# Breadboard.net
KiCad netlist of a schematic drawn in EAGLE
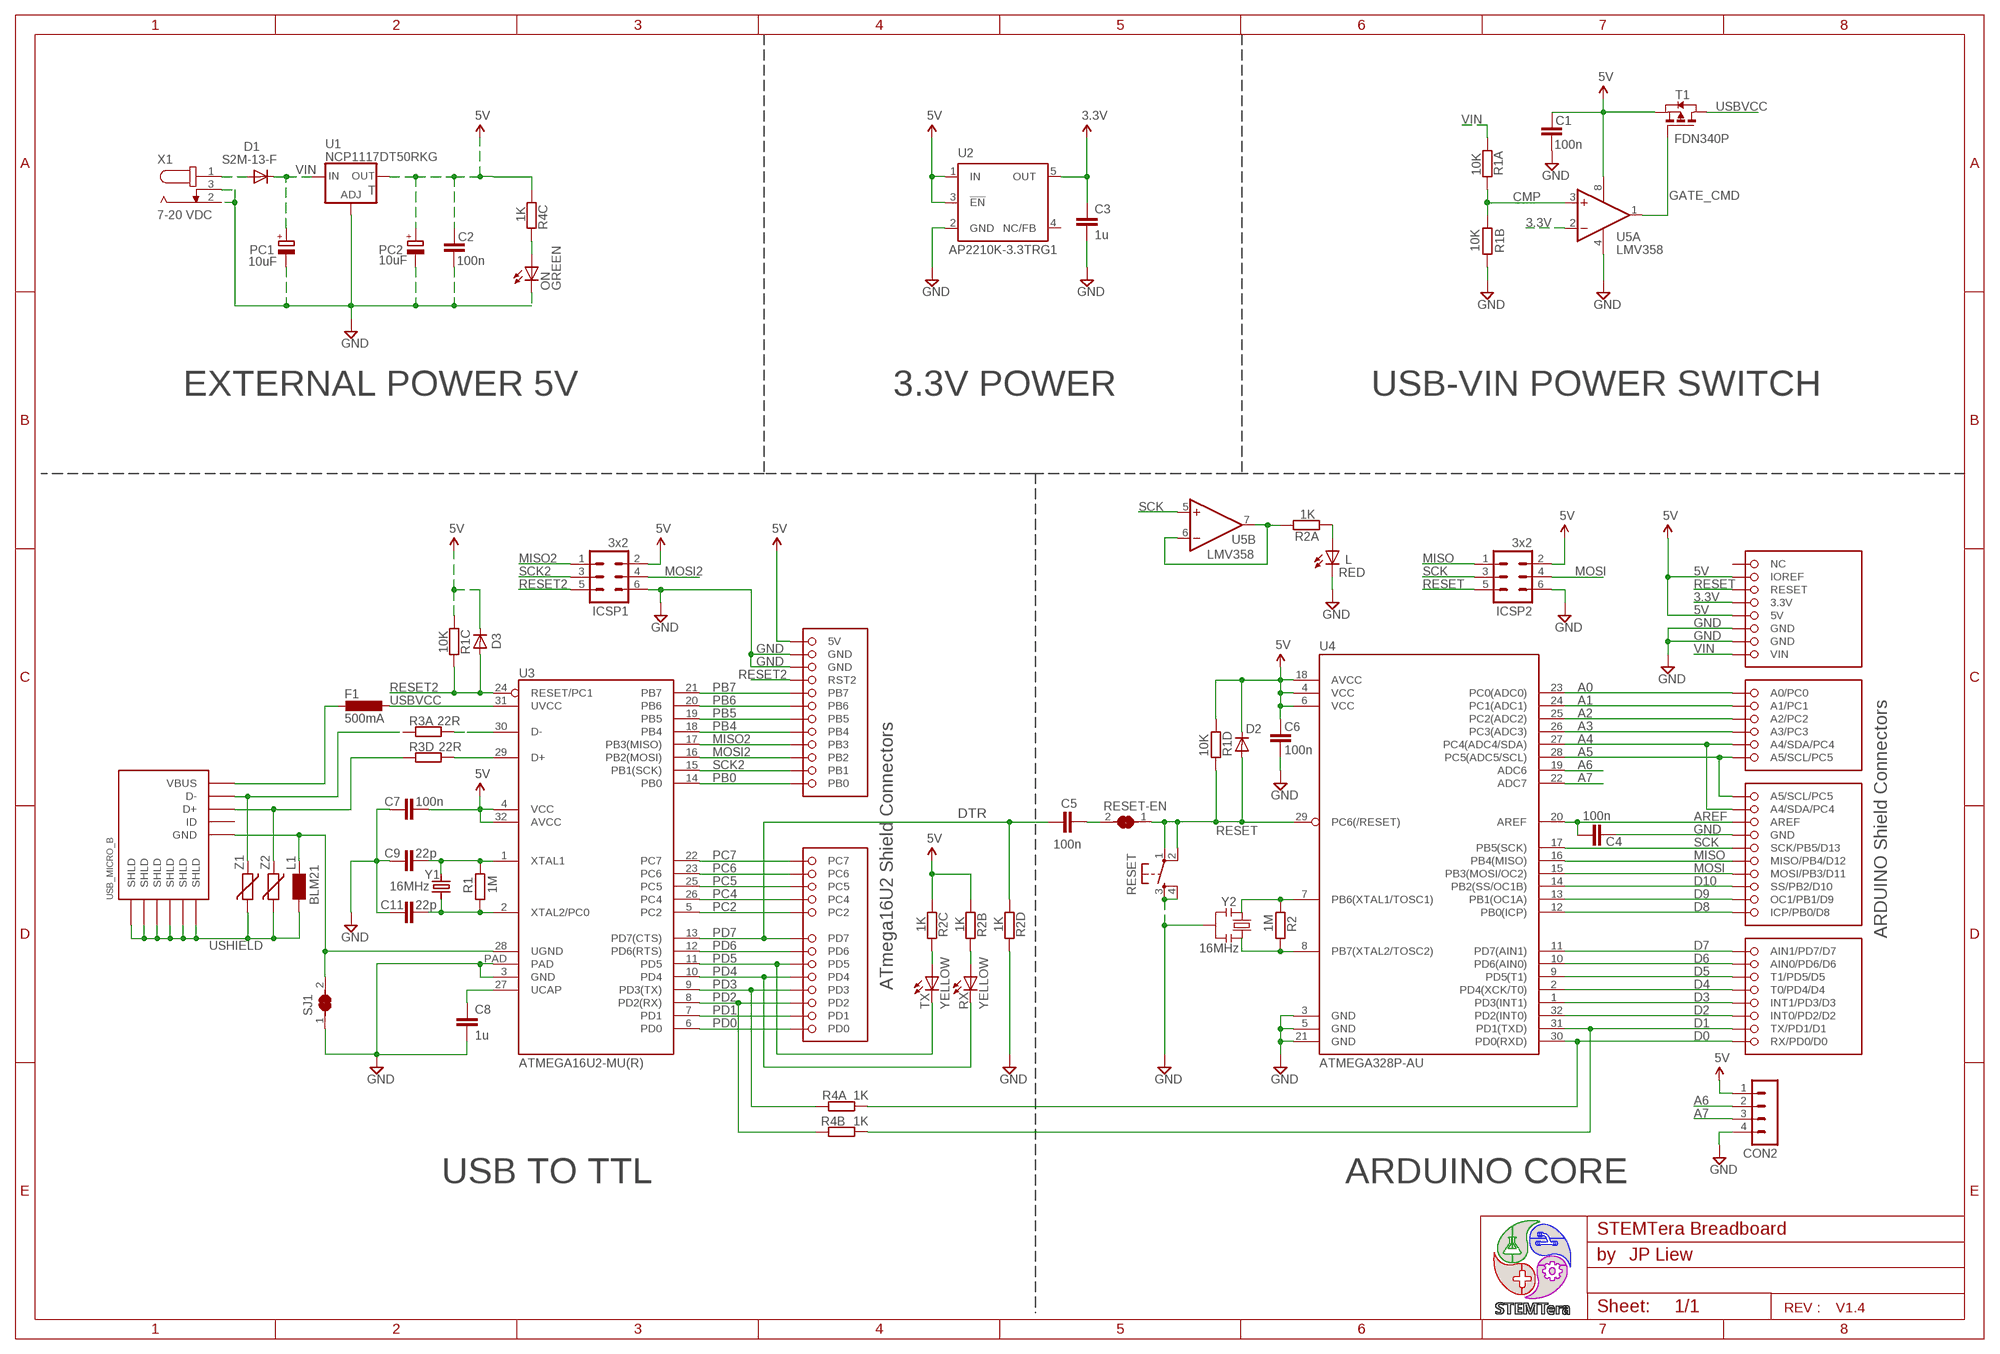
[diagram p0: schematic, sheet 1]

(export (version "E")
  (design (tool "Eeschema 10.0.6"))
  (components
    (comp (ref "C1")
      (value "100n")
      (footprint "eagle-import:C0603")
      (description "CAP CER 0.1UF 50V X7R 0603")
      (fields (field (name "MF") "Yageo") (field (name "MPN") "CC0603KRX7R9BB104"))
      (libsource (lib "eagle-import") (part "C-EUC0603"))
    )
    (comp (ref "C2")
      (value "100n")
      (footprint "eagle-import:C0603")
      (description "CAP CER 0.1UF 50V X7R 0603")
      (fields (field (name "MF") "Yageo") (field (name "MPN") "CC0603KRX7R9BB104"))
      (libsource (lib "eagle-import") (part "C-EUC0603"))
    )
    (comp (ref "C3")
      (value "1u")
      (footprint "eagle-import:C0603")
      (description "CAP CER 1UF 10V X5R 0603")
      (fields (field (name "MF") "Yageo") (field (name "MPN") "CC0603KRX5R6BB105"))
      (libsource (lib "eagle-import") (part "C-EUC0603"))
    )
    (comp (ref "C4")
      (value "100n")
      (footprint "eagle-import:C0603")
      (description "CAP CER 0.1UF 50V X7R 0603")
      (fields (field (name "MF") "Yageo") (field (name "MPN") "CC0603KRX7R9BB104"))
      (libsource (lib "eagle-import") (part "C-EUC0603"))
    )
    (comp (ref "C5")
      (value "100n")
      (footprint "eagle-import:C0603")
      (description "CAP CER 0.1UF 50V X7R 0603")
      (fields (field (name "MF") "Yageo") (field (name "MPN") "CC0603KRX7R9BB104"))
      (libsource (lib "eagle-import") (part "C-EUC0603"))
    )
    (comp (ref "C6")
      (value "100n")
      (footprint "eagle-import:C0603")
      (description "CAP CER 0.1UF 50V X7R 0603")
      (fields (field (name "MF") "Yageo") (field (name "MPN") "CC0603KRX7R9BB104"))
      (libsource (lib "eagle-import") (part "C-EUC0603"))
    )
    (comp (ref "C7")
      (value "100n")
      (footprint "eagle-import:C0603")
      (description "CAP CER 0.1UF 50V X7R 0603")
      (fields (field (name "MF") "Yageo") (field (name "MPN") "CC0603KRX7R9BB104"))
      (libsource (lib "eagle-import") (part "C-EUC0603"))
    )
    (comp (ref "C8")
      (value "1u")
      (footprint "eagle-import:C0603")
      (description "CAP CER 1UF 10V X5R 0603")
      (fields (field (name "MF") "Yageo") (field (name "MPN") "CC0603KRX5R6BB105"))
      (libsource (lib "eagle-import") (part "C-EUC0603"))
    )
    (comp (ref "C9")
      (value "22p")
      (footprint "eagle-import:C0603")
      (description "CAP CER 22PF 50V NP0 0603")
      (fields (field (name "MF") "AVX") (field (name "MPN") "06035A220JAT2A"))
      (libsource (lib "eagle-import") (part "C-EUC0603"))
    )
    (comp (ref "C11")
      (value "22p")
      (footprint "eagle-import:C0603")
      (description "CAP CER 22PF 50V NP0 0603")
      (fields (field (name "MF") "AVX") (field (name "MPN") "06035A220JAT2A"))
      (libsource (lib "eagle-import") (part "C-EUC0603"))
    )
    (comp (ref "CON1")
      (value "STEMTERA")
      (footprint "eagle-import:STEMTERA")
      (fields (field (name "MF") "NOT INSTALLED") (field (name "MPN") "NOT INSTALLED"))
      (libsource (lib "eagle-import") (part "STEMTERA"))
    )
    (comp (ref "CON2")
      (value "MA04-1")
      (footprint "eagle-import:MA04-1-SMD")
      (libsource (lib "eagle-import") (part "MA04-1"))
    )
    (comp (ref "D1")
      (value "S2M-13-F")
      (footprint "eagle-import:SMB")
      (description "DIODE GEN PURP 1KV 1.5A SMB")
      (fields (field (name "MF") "Diodes Inc"))
      (libsource (lib "eagle-import") (part "DIODE-SMB"))
    )
    (comp (ref "D2")
      (value "CD1206-S01575")
      (footprint "eagle-import:MINIMELF")
      (description "DIODE GEN PURP 100V 150MA 1206")
      (fields (field (name "MF") "Bourns Inc"))
      (libsource (lib "eagle-import") (part "DIODE-MINIMELF"))
    )
    (comp (ref "D3")
      (value "CD1206-S01575")
      (footprint "eagle-import:MINIMELF")
      (description "DIODE GEN PURP 100V 150MA 1206")
      (fields (field (name "MF") "Bourns Inc"))
      (libsource (lib "eagle-import") (part "DIODE-MINIMELF"))
    )
    (comp (ref "F1")
      (value "500mA")
      (footprint "eagle-import:L1812")
      (description "PTC RESETTABLE .50A 15V 1812")
      (fields (field (name "MF") "Bourns Inc") (field (name "MPN") "MF-MSMF050-2"))
      (libsource (lib "eagle-import") (part "L-EUL1812"))
    )
    (comp (ref "ICSP1")
      (value "3x2")
      (footprint "eagle-import:MA03-2")
      (description "ATmega16U2 ISP Conn")
      (fields (field (name "MF") "NOT INSTALLED") (field (name "MPN") "NOT INSTALLED"))
      (libsource (lib "eagle-import") (part "MA03-2"))
    )
    (comp (ref "ICSP2")
      (value "3x2")
      (footprint "eagle-import:MA03-2")
      (description "ATmega328 ISP Conn")
      (fields (field (name "MF") "NOT INSTALLED") (field (name "MPN") "NOT INSTALLED"))
      (libsource (lib "eagle-import") (part "MA03-2"))
    )
    (comp (ref "L")
      (value "RED")
      (footprint "eagle-import:LED3MM")
      (description "LED, 2MM, RED, 8MCD, 617NM")
      (fields (field (name "MF") "Kingbright") (field (name "MPN") "L-13ID"))
      (libsource (lib "eagle-import") (part "LED3MM"))
    )
    (comp (ref "L1")
      (value "BLM21")
      (footprint "eagle-import:0805")
      (description "FERRITE CHIP 220 OHM 0805")
      (fields (field (name "MF") "Murata") (field (name "MPN") "BLM21PG221SN1D"))
      (libsource (lib "eagle-import") (part "WE-CBF-0805"))
    )
    (comp (ref "ON")
      (value "GREEN")
      (footprint "eagle-import:LED3MM")
      (description "LED, GREEN, 2MM, 12MCD, 568NM")
      (fields (field (name "MF") "Kingbright") (field (name "MPN") "L-13GD"))
      (libsource (lib "eagle-import") (part "LED3MM"))
    )
    (comp (ref "PC1")
      (value "10uF")
      (footprint "eagle-import:CT6032")
      (description "CAP TANT 10UF 25V 20%")
      (fields (field (name "MF") "Kemet") (field (name "MPN") "T491C106M025AT7280"))
      (libsource (lib "eagle-import") (part "CAP_POL-CT6032"))
    )
    (comp (ref "PC2")
      (value "10uF")
      (footprint "eagle-import:CT6032")
      (description "CAP TANT 10UF 25V 20%")
      (fields (field (name "MF") "Kemet") (field (name "MPN") "T491C106M025AT7280"))
      (libsource (lib "eagle-import") (part "CAP_POL-CT6032"))
    )
    (comp (ref "R1")
      (value "1M")
      (footprint "eagle-import:R0603")
      (description "RES SMD 1M OHM 1% 1/10W 0603")
      (fields (field (name "MF") "Yageo") (field (name "MPN") "RC0603FR-071ML"))
      (libsource (lib "eagle-import") (part "R-EU_R0603"))
    )
    (comp (ref "R1A")
      (value "10K")
      (footprint "eagle-import:R0603")
      (description "RES SMD 10K OHM 1% 1/10W 0603")
      (fields (field (name "MF") "Yageo") (field (name "MPN") "RC0603FR-0710KL"))
      (libsource (lib "eagle-import") (part "R-EU_R0603"))
    )
    (comp (ref "R1B")
      (value "10K")
      (footprint "eagle-import:R0603")
      (description "RES SMD 10K OHM 1% 1/10W 0603")
      (fields (field (name "MF") "Yageo") (field (name "MPN") "RC0603FR-0710KL"))
      (libsource (lib "eagle-import") (part "R-EU_R0603"))
    )
    (comp (ref "R1C")
      (value "10K")
      (footprint "eagle-import:R0603")
      (description "RES SMD 10K OHM 1% 1/10W 0603")
      (fields (field (name "MF") "Yageo") (field (name "MPN") "RC0603FR-0710KL"))
      (libsource (lib "eagle-import") (part "R-EU_R0603"))
    )
    (comp (ref "R1D")
      (value "10K")
      (footprint "eagle-import:R0603")
      (description "RES SMD 10K OHM 1% 1/10W 0603")
      (fields (field (name "MF") "Yageo") (field (name "MPN") "RC0603FR-0710KL"))
      (libsource (lib "eagle-import") (part "R-EU_R0603"))
    )
    (comp (ref "R2")
      (value "1M")
      (footprint "eagle-import:R0603")
      (description "RES SMD 1M OHM 1% 1/10W 0603")
      (fields (field (name "MF") "Yageo") (field (name "MPN") "RC0603FR-071ML"))
      (libsource (lib "eagle-import") (part "R-EU_R0603"))
    )
    (comp (ref "R2A")
      (value "1K")
      (footprint "eagle-import:R0603")
      (description "RES SMD 1K OHM 1% 1/10W 0603")
      (fields (field (name "MF") "Yageo") (field (name "MPN") "RC0603FR-071KL"))
      (libsource (lib "eagle-import") (part "R-EU_R0603"))
    )
    (comp (ref "R2B")
      (value "1K")
      (footprint "eagle-import:R0603")
      (description "RES SMD 1K OHM 1% 1/10W 0603")
      (fields (field (name "MF") "Yageo") (field (name "MPN") "RC0603FR-071KL"))
      (libsource (lib "eagle-import") (part "R-EU_R0603"))
    )
    (comp (ref "R2C")
      (value "1K")
      (footprint "eagle-import:R0603")
      (description "RES SMD 1K OHM 1% 1/10W 0603")
      (fields (field (name "MF") "Yageo") (field (name "MPN") "RC0603FR-071KL"))
      (libsource (lib "eagle-import") (part "R-EU_R0603"))
    )
    (comp (ref "R2D")
      (value "1K")
      (footprint "eagle-import:R0603")
      (description "RES SMD 1K OHM 1% 1/10W 0603")
      (fields (field (name "MF") "Yageo") (field (name "MPN") "RC0603FR-071KL"))
      (libsource (lib "eagle-import") (part "R-EU_R0603"))
    )
    (comp (ref "R3A")
      (value "22R")
      (footprint "eagle-import:R0603")
      (description "RES SMD 22 OHM 1% 1/10W 0603")
      (fields (field (name "MF") "Yageo") (field (name "MPN") "RC0603FR-0722RL"))
      (libsource (lib "eagle-import") (part "R-EU_R0603"))
    )
    (comp (ref "R3D")
      (value "22R")
      (footprint "eagle-import:R0603")
      (description "RES SMD 22 OHM 1% 1/10W 0603")
      (fields (field (name "MF") "Yageo") (field (name "MPN") "RC0603FR-0722RL"))
      (libsource (lib "eagle-import") (part "R-EU_R0603"))
    )
    (comp (ref "R4A")
      (value "1K")
      (footprint "eagle-import:R0603")
      (description "RES SMD 1K OHM 1% 1/10W 0603")
      (fields (field (name "MF") "Yageo") (field (name "MPN") "RC0603FR-071KL"))
      (libsource (lib "eagle-import") (part "R-EU_R0603"))
    )
    (comp (ref "R4B")
      (value "1K")
      (footprint "eagle-import:R0603")
      (description "RES SMD 1K OHM 1% 1/10W 0603")
      (fields (field (name "MF") "Yageo") (field (name "MPN") "RC0603FR-071KL"))
      (libsource (lib "eagle-import") (part "R-EU_R0603"))
    )
    (comp (ref "R4C")
      (value "1K")
      (footprint "eagle-import:R0603")
      (description "RES SMD 1K OHM 1% 1/10W 0603")
      (fields (field (name "MF") "Yageo") (field (name "MPN") "RC0603FR-071KL"))
      (libsource (lib "eagle-import") (part "R-EU_R0603"))
    )
    (comp (ref "RESET")
      (value "PUSH_BUTTON-ESWITCH_TL6120DF300QG")
      (footprint "eagle-import:PUSH_BUTTON-ESWITCH_TL6120DF300QG")
      (fields (field (name "MF") "E-Switch") (field (name "MPN") "TL6120DF300QG"))
      (libsource (lib "eagle-import") (part "PUSH_BUTTON-ESWITCH_TL6120DF300QG"))
    )
    (comp (ref "RESET-EN")
      (value "Jumper")
      (footprint "eagle-import:SOLDER_JUMPER_NC")
      (description "RESET ENABLE PCB JUMPER")
      (fields (field (name "MF") "NOT INSTALLED"))
      (libsource (lib "eagle-import") (part "SOLDER_JUMPER_NC"))
    )
    (comp (ref "RX")
      (value "YELLOW")
      (footprint "eagle-import:LED3MM")
      (description "LED, 2MM, YELLOW, 8MCD, 588NM")
      (fields (field (name "MF") "Kingbright") (field (name "MPN") "L-13YD"))
      (libsource (lib "eagle-import") (part "LED3MM"))
    )
    (comp (ref "SJ1")
      (value "Jumper")
      (footprint "eagle-import:SOLDER_JUMPER_NC")
      (description "USB SHIELD GROUND PCB JUMPER")
      (fields (field (name "MF") "NOT INSTALLED"))
      (libsource (lib "eagle-import") (part "SOLDER_JUMPER_NC"))
    )
    (comp (ref "T1")
      (value "FDN340P")
      (footprint "eagle-import:SOT-23")
      (description "MOSFET P-CH 20V 2A SSOT3")
      (fields (field (name "MF") "Fairchild") (field (name "MPN") "FDN340P"))
      (libsource (lib "eagle-import") (part "PMOSSOT23"))
    )
    (comp (ref "TX")
      (value "YELLOW")
      (footprint "eagle-import:LED3MM")
      (description "LED, YELLOW, 2MM, 8MCD, 590NM")
      (fields (field (name "MF") "Kingbright") (field (name "MPN") "L-13YD"))
      (libsource (lib "eagle-import") (part "LED3MM"))
    )
    (comp (ref "U1")
      (value "NCP1117DT50RKG")
      (footprint "eagle-import:DPACK")
      (description "IC REG LDO 5V 1A DPAK")
      (fields (field (name "MF") "ON Semiconductor"))
      (libsource (lib "eagle-import") (part "LD117A?DT-TR"))
    )
    (comp (ref "U2")
      (value "AP2210K-3.3TRG1")
      (footprint "eagle-import:SOT23-DBV")
      (description "IC REG LDO 3.3V 0.3A SOT25")
      (fields
        (field (name "MF") "TEXAS INSTRUMENTS")
        (field (name "MPN") "TPS77001DBVT")
        (field (name "MF_1") "Diodes Inc")
        (field (name "MPN_1") "AP2210K-3.3TRG1")
      )
      (libsource (lib "eagle-import") (part "TPS77001"))
    )
    (comp (ref "U3")
      (value "ATMEGA16U2-MU(R)")
      (footprint "eagle-import:QFN32")
      (description "IC MCU 8BIT 16KB FLASH 32QFN")
      (fields (field (name "MF") "Atmel") (field (name "MPN") "ATMEGA16U2-MU"))
      (libsource (lib "eagle-import") (part "ATMEGAXXU2-MU"))
    )
    (comp (ref "U4")
      (value "ATMEGA328P-AU")
      (footprint "eagle-import:TQFP32-7MM_0.8MM")
      (description "IC MCU 8BIT 32KB FLASH 32TQFP")
      (fields (field (name "MF") "Atmel") (field (name "MPN") "ATmega328P-AUR"))
      (libsource (lib "eagle-import") (part "ATMEGAXX8-32PIN"))
    )
    (comp (ref "U5")
      (value "LMV358")
      (footprint "eagle-import:SOIC08_3.8MM")
      (description "IC OPAMP GP 1MHZ RRO 8SOP")
      (fields
        (field (name "MF") "Diodes Incorporated")
        (field (name "MPN") "LMV358SG-13")
        (field (name "OC_DIGIKEY") "LMV358SG-13DITR-ND")
        (field (name "URL") "http://www.digikey.com/product-detail/en/LMV358SG-13/LMV358SG-13DITR-ND/2182560")
      )
      (libsource (lib "eagle-import") (part "LM358-SO8"))
    )
    (comp (ref "USB_MICRO_B")
      (value "CONN_USB-FCI_10118193-0001LF")
      (footprint "eagle-import:CONN_USB_MICRO_B_10118193-0001LF")
      (fields
        (field (name "MF") "FCI")
        (field (name "MPN") "10118193-0001LF")
        (field (name "MPN_1") "10118193-0001LF")
      )
      (libsource (lib "eagle-import") (part "CONN_USB-FCI_10118193-0001LF"))
    )
    (comp (ref "X1")
      (value "CONN_JACK-SINGLE_SIDED")
      (footprint "eagle-import:CONN_JACK_PJ-051A-SINGLE_SIDED")
      (fields (field (name "MF") "CUI Inc") (field (name "MPN") "PJ-051A"))
      (libsource (lib "eagle-import") (part "CONN_JACK-SINGLE_SIDED"))
    )
    (comp (ref "Y1")
      (value "16MHz")
      (footprint "eagle-import:HC49US-SMD-2.5MM")
      (description "Crystal 16.0000MHz 20ppm 18pF")
      (fields (field (name "MF") "Abracon") (field (name "MPN") "ABLS3-16.000MHZ-D4Y-T"))
      (libsource (lib "eagle-import") (part "CRYSTAL-HC49US_2.5MM"))
    )
    (comp (ref "Y2")
      (value "16MHz")
      (footprint "eagle-import:CSTCE_V")
      (description "CER RESONATOR 16.0MHZ SMD")
      (fields (field (name "MF") "Murata") (field (name "MPN") "CSTCE16M0V53-R0"))
      (libsource (lib "eagle-import") (part "RESONATORS-CSCTE_V"))
    )
    (comp (ref "Z1")
      (value "VARISTORCN0603")
      (footprint "eagle-import:CT_CN0603")
      (description "VARISTOR 0603")
      (fields (field (name "MF") "Bourns Inc") (field (name "MPN") "CG0603MLC-05E"))
      (libsource (lib "eagle-import") (part "VARISTORCN0603"))
    )
    (comp (ref "Z2")
      (value "VARISTORCN0603")
      (footprint "eagle-import:CT_CN0603")
      (description "VARISTOR 0603")
      (fields (field (name "MF") "Bourns Inc") (field (name "MPN") "CG0603MLC-05E"))
      (libsource (lib "eagle-import") (part "VARISTORCN0603"))
    )
  )
  (nets
    (net (code "1") (name "/A0") (class "Default")
      (node (ref "CON1") (pin "A0") (pinfunction "A0/PC0_A0") (pintype "bidirectional"))
      (node (ref "U4") (pin "23") (pinfunction "PC0(ADC0)_23") (pintype "bidirectional"))
    )
    (net (code "2") (name "/A1") (class "Default")
      (node (ref "CON1") (pin "A1") (pinfunction "A1/PC1_A1") (pintype "bidirectional"))
      (node (ref "U4") (pin "24") (pinfunction "PC1(ADC1)_24") (pintype "bidirectional"))
    )
    (net (code "3") (name "/A2") (class "Default")
      (node (ref "CON1") (pin "A2") (pinfunction "A2/PC2_A2") (pintype "bidirectional"))
      (node (ref "U4") (pin "25") (pinfunction "PC2(ADC2)_25") (pintype "bidirectional"))
    )
    (net (code "4") (name "/A3") (class "Default")
      (node (ref "CON1") (pin "A3") (pinfunction "A3/PC3_A3") (pintype "bidirectional"))
      (node (ref "U4") (pin "26") (pinfunction "PC3(ADC3)_26") (pintype "bidirectional"))
    )
    (net (code "5") (name "/A4") (class "Default")
      (node (ref "CON1") (pin "A4@1") (pinfunction "A4/SDA/PC4_A4@1") (pintype "bidirectional"))
      (node (ref "CON1") (pin "A4@2") (pinfunction "A4/SDA/PC4_A4@2") (pintype "bidirectional"))
      (node (ref "U4") (pin "27") (pinfunction "PC4(ADC4/SDA)_27") (pintype "bidirectional"))
    )
    (net (code "6") (name "/A5") (class "Default")
      (node (ref "CON1") (pin "A5@1") (pinfunction "A5/SCL/PC5_A5@1") (pintype "bidirectional"))
      (node (ref "CON1") (pin "A5@2") (pinfunction "A5/SCL/PC5_A5@2") (pintype "bidirectional"))
      (node (ref "U4") (pin "28") (pinfunction "PC5(ADC5/SCL)_28") (pintype "bidirectional"))
    )
    (net (code "7") (name "/A6") (class "Default")
      (node (ref "CON2") (pin "2") (pinfunction "2_2") (pintype "passive"))
      (node (ref "U4") (pin "19") (pinfunction "ADC6_19") (pintype "bidirectional"))
    )
    (net (code "8") (name "/A7") (class "Default")
      (node (ref "CON2") (pin "3") (pinfunction "3_3") (pintype "passive"))
      (node (ref "U4") (pin "22") (pinfunction "ADC7_22") (pintype "bidirectional"))
    )
    (net (code "9") (name "/AREF") (class "Default")
      (node (ref "C4") (pin "2") (pinfunction "2_2") (pintype "passive"))
      (node (ref "CON1") (pin "AREF") (pinfunction "AREF_AREF") (pintype "passive"))
      (node (ref "U4") (pin "20") (pinfunction "AREF_20") (pintype "bidirectional"))
    )
    (net (code "10") (name "/CMP") (class "Default")
      (node (ref "R1A") (pin "1") (pinfunction "1_1") (pintype "passive"))
      (node (ref "R1B") (pin "2") (pinfunction "2_2") (pintype "passive"))
      (node (ref "U5") (pin "3") (pinfunction "+IN_3") (pintype "input"))
    )
    (net (code "11") (name "/D0") (class "Default")
      (node (ref "CON1") (pin "D0") (pinfunction "RX/PD0/D0_D0") (pintype "bidirectional"))
      (node (ref "R4A") (pin "2") (pinfunction "2_2") (pintype "passive"))
      (node (ref "U4") (pin "30") (pinfunction "PD0(RXD)_30") (pintype "bidirectional"))
    )
    (net (code "12") (name "/D1") (class "Default")
      (node (ref "CON1") (pin "D1") (pinfunction "TX/PD1/D1_D1") (pintype "bidirectional"))
      (node (ref "R4B") (pin "2") (pinfunction "2_2") (pintype "passive"))
      (node (ref "U4") (pin "31") (pinfunction "PD1(TXD)_31") (pintype "bidirectional"))
    )
    (net (code "13") (name "/D2") (class "Default")
      (node (ref "CON1") (pin "D2") (pinfunction "INT0/PD2/D2_D2") (pintype "bidirectional"))
      (node (ref "U4") (pin "32") (pinfunction "PD2(INT0)_32") (pintype "bidirectional"))
    )
    (net (code "14") (name "/D3") (class "Default")
      (node (ref "CON1") (pin "D3") (pinfunction "INT1/PD3/D3_D3") (pintype "bidirectional"))
      (node (ref "U4") (pin "1") (pinfunction "PD3(INT1)_1") (pintype "bidirectional"))
    )
    (net (code "15") (name "/D4") (class "Default")
      (node (ref "CON1") (pin "D4") (pinfunction "T0/PD4/D4_D4") (pintype "bidirectional"))
      (node (ref "U4") (pin "2") (pinfunction "PD4(XCK/T0)_2") (pintype "bidirectional"))
    )
    (net (code "16") (name "/D5") (class "Default")
      (node (ref "CON1") (pin "D5") (pinfunction "T1/PD5/D5_D5") (pintype "bidirectional"))
      (node (ref "U4") (pin "9") (pinfunction "PD5(T1)_9") (pintype "bidirectional"))
    )
    (net (code "17") (name "/D6") (class "Default")
      (node (ref "CON1") (pin "D6") (pinfunction "AIN0/PD6/D6_D6") (pintype "bidirectional"))
      (node (ref "U4") (pin "10") (pinfunction "PD6(AIN0)_10") (pintype "bidirectional"))
    )
    (net (code "18") (name "/D7") (class "Default")
      (node (ref "CON1") (pin "D7") (pinfunction "AIN1/PD7/D7_D7") (pintype "bidirectional"))
      (node (ref "U4") (pin "11") (pinfunction "PD7(AIN1)_11") (pintype "bidirectional"))
    )
    (net (code "19") (name "/D8") (class "Default")
      (node (ref "CON1") (pin "D8") (pinfunction "ICP/PB0/D8_D8") (pintype "bidirectional"))
      (node (ref "U4") (pin "12") (pinfunction "PB0(ICP)_12") (pintype "bidirectional"))
    )
    (net (code "20") (name "/D9") (class "Default")
      (node (ref "CON1") (pin "D9") (pinfunction "OC1/PB1/D9_D9") (pintype "bidirectional"))
      (node (ref "U4") (pin "13") (pinfunction "PB1(OC1A)_13") (pintype "bidirectional"))
    )
    (net (code "21") (name "/D10") (class "Default")
      (node (ref "CON1") (pin "D10") (pinfunction "SS/PB2/D10_D10") (pintype "bidirectional"))
      (node (ref "U4") (pin "14") (pinfunction "PB2(SS/OC1B)_14") (pintype "bidirectional"))
    )
    (net (code "22") (name "/GATE_CMD") (class "Default")
      (node (ref "T1") (pin "3") (pinfunction "G_3") (pintype "passive"))
      (node (ref "U5") (pin "1") (pinfunction "OUT_1") (pintype "output"))
    )
    (net (code "23") (name "/MISO") (class "Default")
      (node (ref "CON1") (pin "D12") (pinfunction "MISO/PB4/D12_D12") (pintype "bidirectional"))
      (node (ref "ICSP2") (pin "1") (pinfunction "1_1") (pintype "passive"))
      (node (ref "U4") (pin "16") (pinfunction "PB4(MISO)_16") (pintype "bidirectional"))
    )
    (net (code "24") (name "/MISO2") (class "Default")
      (node (ref "CON1") (pin "PB3") (pinfunction "PB3_PB3") (pintype "bidirectional"))
      (node (ref "ICSP1") (pin "1") (pinfunction "1_1") (pintype "passive"))
      (node (ref "U3") (pin "17") (pinfunction "PB3(MISO)_17") (pintype "bidirectional"))
    )
    (net (code "25") (name "/MOSI") (class "Default")
      (node (ref "CON1") (pin "D11") (pinfunction "MOSI/PB3/D11_D11") (pintype "bidirectional"))
      (node (ref "ICSP2") (pin "4") (pinfunction "4_4") (pintype "passive"))
      (node (ref "U4") (pin "15") (pinfunction "PB3(MOSI/OC2)_15") (pintype "bidirectional"))
    )
    (net (code "26") (name "/MOSI2") (class "Default")
      (node (ref "CON1") (pin "PB2") (pinfunction "PB2_PB2") (pintype "bidirectional"))
      (node (ref "ICSP1") (pin "4") (pinfunction "4_4") (pintype "passive"))
      (node (ref "U3") (pin "16") (pinfunction "PB2(MOSI)_16") (pintype "bidirectional"))
    )
    (net (code "27") (name "/PB0") (class "Default")
      (node (ref "CON1") (pin "PB0") (pinfunction "PB0_PB0") (pintype "bidirectional"))
      (node (ref "U3") (pin "14") (pinfunction "PB0_14") (pintype "bidirectional"))
    )
    (net (code "28") (name "/PB4") (class "Default")
      (node (ref "CON1") (pin "PB4") (pinfunction "PB4_PB4") (pintype "bidirectional"))
      (node (ref "U3") (pin "18") (pinfunction "PB4_18") (pintype "bidirectional"))
    )
    (net (code "29") (name "/PB5") (class "Default")
      (node (ref "CON1") (pin "PB5") (pinfunction "PB5_PB5") (pintype "bidirectional"))
      (node (ref "U3") (pin "19") (pinfunction "PB5_19") (pintype "bidirectional"))
    )
    (net (code "30") (name "/PB6") (class "Default")
      (node (ref "CON1") (pin "PB6") (pinfunction "PB6_PB6") (pintype "bidirectional"))
      (node (ref "U3") (pin "20") (pinfunction "PB6_20") (pintype "bidirectional"))
    )
    (net (code "31") (name "/PB7") (class "Default")
      (node (ref "CON1") (pin "PB7") (pinfunction "PB7_PB7") (pintype "bidirectional"))
      (node (ref "U3") (pin "21") (pinfunction "PB7_21") (pintype "bidirectional"))
    )
    (net (code "32") (name "/PC2") (class "Default")
      (node (ref "CON1") (pin "PC2") (pinfunction "PC2_PC2") (pintype "bidirectional"))
      (node (ref "U3") (pin "5") (pinfunction "PC2_5") (pintype "bidirectional"))
    )
    (net (code "33") (name "/PC4") (class "Default")
      (node (ref "CON1") (pin "PC4") (pinfunction "PC4_PC4") (pintype "bidirectional"))
      (node (ref "U3") (pin "26") (pinfunction "PC4_26") (pintype "bidirectional"))
    )
    (net (code "34") (name "/PC5") (class "Default")
      (node (ref "CON1") (pin "PC5") (pinfunction "PC5_PC5") (pintype "bidirectional"))
      (node (ref "U3") (pin "25") (pinfunction "PC5_25") (pintype "bidirectional"))
    )
    (net (code "35") (name "/PC6") (class "Default")
      (node (ref "CON1") (pin "PC6") (pinfunction "PC6_PC6") (pintype "bidirectional"))
      (node (ref "U3") (pin "23") (pinfunction "PC6_23") (pintype "bidirectional"))
    )
    (net (code "36") (name "/PC7") (class "Default")
      (node (ref "CON1") (pin "PC7") (pinfunction "PC7_PC7") (pintype "bidirectional"))
      (node (ref "U3") (pin "22") (pinfunction "PC7_22") (pintype "bidirectional"))
    )
    (net (code "37") (name "/PD0") (class "Default")
      (node (ref "CON1") (pin "PD0") (pinfunction "PD0_PD0") (pintype "bidirectional"))
      (node (ref "U3") (pin "6") (pinfunction "PD0_6") (pintype "bidirectional"))
    )
    (net (code "38") (name "/PD1") (class "Default")
      (node (ref "CON1") (pin "PD1") (pinfunction "PD1_PD1") (pintype "bidirectional"))
      (node (ref "U3") (pin "7") (pinfunction "PD1_7") (pintype "bidirectional"))
    )
    (net (code "39") (name "/PD2") (class "Default")
      (node (ref "CON1") (pin "PD2") (pinfunction "PD2_PD2") (pintype "bidirectional"))
      (node (ref "R4B") (pin "1") (pinfunction "1_1") (pintype "passive"))
      (node (ref "U3") (pin "8") (pinfunction "PD2(RX)_8") (pintype "bidirectional"))
    )
    (net (code "40") (name "/PD3") (class "Default")
      (node (ref "CON1") (pin "PD3") (pinfunction "PD3_PD3") (pintype "bidirectional"))
      (node (ref "R4A") (pin "1") (pinfunction "1_1") (pintype "passive"))
      (node (ref "U3") (pin "9") (pinfunction "PD3(TX)_9") (pintype "bidirectional"))
    )
    (net (code "41") (name "/PD4") (class "Default")
      (node (ref "CON1") (pin "PD4") (pinfunction "PD4_PD4") (pintype "bidirectional"))
      (node (ref "RX") (pin "K") (pinfunction "C_K") (pintype "passive"))
      (node (ref "U3") (pin "10") (pinfunction "PD4_10") (pintype "bidirectional"))
    )
    (net (code "42") (name "/PD5") (class "Default")
      (node (ref "CON1") (pin "PD5") (pinfunction "PD5_PD5") (pintype "bidirectional"))
      (node (ref "TX") (pin "K") (pinfunction "C_K") (pintype "passive"))
      (node (ref "U3") (pin "11") (pinfunction "PD5_11") (pintype "bidirectional"))
    )
    (net (code "43") (name "/PD6") (class "Default")
      (node (ref "CON1") (pin "PD6") (pinfunction "PD6_PD6") (pintype "bidirectional"))
      (node (ref "U3") (pin "12") (pinfunction "PD6(RTS)_12") (pintype "bidirectional"))
    )
    (net (code "44") (name "/PD7") (class "Default")
      (node (ref "C5") (pin "1") (pinfunction "1_1") (pintype "passive"))
      (node (ref "CON1") (pin "PD7") (pinfunction "PD7_PD7") (pintype "bidirectional"))
      (node (ref "R2D") (pin "2") (pinfunction "2_2") (pintype "passive"))
      (node (ref "U3") (pin "13") (pinfunction "PD7(CTS)_13") (pintype "bidirectional"))
    )
    (net (code "45") (name "/RESET") (class "Default")
      (node (ref "CON1") (pin "RESET") (pinfunction "RESET_RESET") (pintype "bidirectional"))
      (node (ref "D2") (pin "A") (pinfunction "A_A") (pintype "passive"))
      (node (ref "ICSP2") (pin "5") (pinfunction "5_5") (pintype "passive"))
      (node (ref "R1D") (pin "1") (pinfunction "1_1") (pintype "passive"))
      (node (ref "RESET") (pin "1") (pinfunction "1_1") (pintype "passive"))
      (node (ref "RESET") (pin "2") (pinfunction "2_2") (pintype "passive"))
      (node (ref "RESET-EN") (pin "1") (pinfunction "1_1") (pintype "passive"))
      (node (ref "U4") (pin "29") (pinfunction "PC6(/RESET)_29") (pintype "bidirectional"))
    )
    (net (code "46") (name "/RESET2") (class "Default")
      (node (ref "CON1") (pin "RST2") (pinfunction "RST2_RST2") (pintype "bidirectional"))
      (node (ref "D3") (pin "A") (pinfunction "A_A") (pintype "passive"))
      (node (ref "ICSP1") (pin "5") (pinfunction "5_5") (pintype "passive"))
      (node (ref "R1C") (pin "1") (pinfunction "1_1") (pintype "passive"))
      (node (ref "U3") (pin "24") (pinfunction "RESET/PC1_24") (pintype "bidirectional"))
    )
    (net (code "47") (name "/SCK") (class "Default")
      (node (ref "CON1") (pin "D13") (pinfunction "SCK/PB5/D13_D13") (pintype "bidirectional"))
      (node (ref "ICSP2") (pin "3") (pinfunction "3_3") (pintype "passive"))
      (node (ref "U4") (pin "17") (pinfunction "PB5(SCK)_17") (pintype "bidirectional"))
      (node (ref "U5") (pin "5") (pinfunction "+IN_5") (pintype "input"))
    )
    (net (code "48") (name "/SCK2") (class "Default")
      (node (ref "CON1") (pin "PB1") (pinfunction "PB1_PB1") (pintype "bidirectional"))
      (node (ref "ICSP1") (pin "3") (pinfunction "3_3") (pintype "passive"))
      (node (ref "U3") (pin "15") (pinfunction "PB1(SCK)_15") (pintype "bidirectional"))
    )
    (net (code "49") (name "/USBVCC") (class "Default")
      (node (ref "F1") (pin "1") (pinfunction "1_1") (pintype "passive"))
      (node (ref "T1") (pin "1") (pinfunction "D_1") (pintype "passive"))
      (node (ref "U3") (pin "31") (pinfunction "UVCC_31") (pintype "power_in"))
    )
    (net (code "50") (name "/USHIELD") (class "Default")
      (node (ref "L1") (pin "2") (pinfunction "2_2") (pintype "passive"))
      (node (ref "USB_MICRO_B") (pin "SHLD@1") (pinfunction "SHLD_SHLD@1") (pintype "passive"))
      (node (ref "USB_MICRO_B") (pin "SHLD@2") (pinfunction "SHLD_SHLD@2") (pintype "passive"))
      (node (ref "USB_MICRO_B") (pin "SHLD@3") (pinfunction "SHLD_SHLD@3") (pintype "passive"))
      (node (ref "USB_MICRO_B") (pin "SHLD@4") (pinfunction "SHLD_SHLD@4") (pintype "passive"))
      (node (ref "USB_MICRO_B") (pin "SHLD@5") (pinfunction "SHLD_SHLD@5") (pintype "passive"))
      (node (ref "USB_MICRO_B") (pin "SHLD@6") (pinfunction "SHLD_SHLD@6") (pintype "passive"))
      (node (ref "Z1") (pin "2") (pinfunction "2_2") (pintype "passive"))
      (node (ref "Z2") (pin "2") (pinfunction "2_2") (pintype "passive"))
    )
    (net (code "51") (name "/VIN") (class "Default")
      (node (ref "CON1") (pin "VIN") (pinfunction "VIN_VIN") (pintype "power_in"))
      (node (ref "D1") (pin "C") (pinfunction "C_C") (pintype "passive"))
      (node (ref "PC1") (pin "+") (pinfunction "+_+") (pintype "passive"))
      (node (ref "R1A") (pin "2") (pinfunction "2_2") (pintype "passive"))
      (node (ref "U1") (pin "3") (pinfunction "IN_3") (pintype "input"))
    )
    (net (code "52") (name "3.3V") (class "Default")
      (node (ref "C3") (pin "1") (pinfunction "1_1") (pintype "passive"))
      (node (ref "CON1") (pin "3.3V") (pinfunction "3.3V_3.3V") (pintype "power_in"))
      (node (ref "U2") (pin "5") (pinfunction "OUT_5") (pintype "passive"))
      (node (ref "U5") (pin "2") (pinfunction "-IN_2") (pintype "input"))
    )
    (net (code "53") (name "5V") (class "Default")
      (node (ref "C1") (pin "2") (pinfunction "2_2") (pintype "passive"))
      (node (ref "C2") (pin "2") (pinfunction "2_2") (pintype "passive"))
      (node (ref "C6") (pin "2") (pinfunction "2_2") (pintype "passive"))
      (node (ref "C7") (pin "2") (pinfunction "2_2") (pintype "passive"))
      (node (ref "CON1") (pin "5V") (pinfunction "5V_5V") (pintype "power_in"))
      (node (ref "CON1") (pin "5V@11") (pinfunction "5V_5V@11") (pintype "power_in"))
      (node (ref "CON1") (pin "IOREF") (pinfunction "IOREF_IOREF") (pintype "bidirectional"))
      (node (ref "CON2") (pin "1") (pinfunction "1_1") (pintype "passive"))
      (node (ref "D2") (pin "C") (pinfunction "C_C") (pintype "passive"))
      (node (ref "D3") (pin "C") (pinfunction "C_C") (pintype "passive"))
      (node (ref "ICSP1") (pin "2") (pinfunction "2_2") (pintype "passive"))
      (node (ref "ICSP2") (pin "2") (pinfunction "2_2") (pintype "passive"))
      (node (ref "PC2") (pin "+") (pinfunction "+_+") (pintype "passive"))
      (node (ref "R1C") (pin "2") (pinfunction "2_2") (pintype "passive"))
      (node (ref "R1D") (pin "2") (pinfunction "2_2") (pintype "passive"))
      (node (ref "R2B") (pin "2") (pinfunction "2_2") (pintype "passive"))
      (node (ref "R2C") (pin "2") (pinfunction "2_2") (pintype "passive"))
      (node (ref "R4C") (pin "2") (pinfunction "2_2") (pintype "passive"))
      (node (ref "T1") (pin "2") (pinfunction "S_2") (pintype "passive"))
      (node (ref "U1") (pin "4") (pinfunction "OUT_4") (pintype "passive"))
      (node (ref "U2") (pin "1") (pinfunction "IN_1") (pintype "input"))
      (node (ref "U2") (pin "3") (pinfunction "~{EN}_3") (pintype "input"))
      (node (ref "U3") (pin "32") (pinfunction "AVCC_32") (pintype "power_in"))
      (node (ref "U3") (pin "4") (pinfunction "VCC_4") (pintype "power_in"))
      (node (ref "U4") (pin "18") (pinfunction "AVCC_18") (pintype "bidirectional"))
      (node (ref "U4") (pin "4") (pinfunction "VCC_4") (pintype "bidirectional"))
      (node (ref "U4") (pin "6") (pinfunction "VCC_6") (pintype "bidirectional"))
      (node (ref "U5") (pin "8") (pinfunction "V+_8") (pintype "power_in"))
    )
    (net (code "54") (name "GND") (class "Default")
      (node (ref "C1") (pin "1") (pinfunction "1_1") (pintype "passive"))
      (node (ref "C11") (pin "1") (pinfunction "1_1") (pintype "passive"))
      (node (ref "C2") (pin "1") (pinfunction "1_1") (pintype "passive"))
      (node (ref "C3") (pin "2") (pinfunction "2_2") (pintype "passive"))
      (node (ref "C4") (pin "1") (pinfunction "1_1") (pintype "passive"))
      (node (ref "C6") (pin "1") (pinfunction "1_1") (pintype "passive"))
      (node (ref "C7") (pin "1") (pinfunction "1_1") (pintype "passive"))
      (node (ref "C8") (pin "2") (pinfunction "2_2") (pintype "passive"))
      (node (ref "C9") (pin "1") (pinfunction "1_1") (pintype "passive"))
      (node (ref "CON1") (pin "GND@1") (pinfunction "GND_GND@1") (pintype "power_in"))
      (node (ref "CON1") (pin "GND@11") (pinfunction "GND_GND@11") (pintype "power_in"))
      (node (ref "CON1") (pin "GND@12") (pinfunction "GND_GND@12") (pintype "power_in"))
      (node (ref "CON1") (pin "GND@2") (pinfunction "GND_GND@2") (pintype "power_in"))
      (node (ref "CON1") (pin "GND@3") (pinfunction "GND_GND@3") (pintype "power_in"))
      (node (ref "CON2") (pin "4") (pinfunction "4_4") (pintype "passive"))
      (node (ref "ICSP1") (pin "6") (pinfunction "6_6") (pintype "passive"))
      (node (ref "ICSP2") (pin "6") (pinfunction "6_6") (pintype "passive"))
      (node (ref "L") (pin "K") (pinfunction "C_K") (pintype "passive"))
      (node (ref "ON") (pin "K") (pinfunction "C_K") (pintype "passive"))
      (node (ref "PC1") (pin "-") (pinfunction "-_-") (pintype "passive"))
      (node (ref "PC2") (pin "-") (pinfunction "-_-") (pintype "passive"))
      (node (ref "R1B") (pin "1") (pinfunction "1_1") (pintype "passive"))
      (node (ref "R2D") (pin "1") (pinfunction "1_1") (pintype "passive"))
      (node (ref "RESET") (pin "3") (pinfunction "3_3") (pintype "passive"))
      (node (ref "RESET") (pin "4") (pinfunction "4_4") (pintype "passive"))
      (node (ref "SJ1") (pin "1") (pinfunction "1_1") (pintype "passive"))
      (node (ref "U1") (pin "1") (pinfunction "ADJ_1") (pintype "input"))
      (node (ref "U2") (pin "2") (pinfunction "GND_2") (pintype "power_in"))
      (node (ref "U3") (pin "3") (pinfunction "GND_3") (pintype "power_in"))
      (node (ref "U3") (pin "PAD") (pinfunction "PAD_PAD") (pintype "power_in"))
      (node (ref "U4") (pin "21") (pinfunction "GND_21") (pintype "bidirectional"))
      (node (ref "U4") (pin "3") (pinfunction "GND_3") (pintype "bidirectional"))
      (node (ref "U4") (pin "5") (pinfunction "GND_5") (pintype "bidirectional"))
      (node (ref "U5") (pin "4") (pinfunction "V-_4") (pintype "power_in"))
      (node (ref "X1") (pin "2") (pinfunction "2_2") (pintype "passive"))
      (node (ref "X1") (pin "3") (pinfunction "3_3") (pintype "passive"))
      (node (ref "Y2") (pin "2") (pinfunction "2_2") (pintype "passive"))
    )
    (net (code "55") (name "Net-(C5-Pad2)") (class "Default")
      (node (ref "C5") (pin "2") (pinfunction "2_2") (pintype "passive"))
      (node (ref "RESET-EN") (pin "2") (pinfunction "2_2") (pintype "passive"))
    )
    (net (code "56") (name "Net-(D1-PadA)") (class "Default")
      (node (ref "D1") (pin "A") (pinfunction "A_A") (pintype "passive"))
      (node (ref "X1") (pin "1") (pinfunction "1_1") (pintype "passive"))
    )
    (net (code "57") (name "Net-(F1-Pad2)") (class "Default")
      (node (ref "F1") (pin "2") (pinfunction "2_2") (pintype "passive"))
      (node (ref "USB_MICRO_B") (pin "VBUS") (pinfunction "VBUS_VBUS") (pintype "power_in"))
    )
    (net (code "58") (name "Net-(L-PadA)") (class "Default")
      (node (ref "L") (pin "A") (pinfunction "A_A") (pintype "passive"))
      (node (ref "R2A") (pin "2") (pinfunction "2_2") (pintype "passive"))
    )
    (net (code "59") (name "Net-(ON-PadA)") (class "Default")
      (node (ref "ON") (pin "A") (pinfunction "A_A") (pintype "passive"))
      (node (ref "R4C") (pin "1") (pinfunction "1_1") (pintype "passive"))
    )
    (net (code "60") (name "Net-(R2B-Pad1)") (class "Default")
      (node (ref "R2B") (pin "1") (pinfunction "1_1") (pintype "passive"))
      (node (ref "RX") (pin "A") (pinfunction "A_A") (pintype "passive"))
    )
    (net (code "61") (name "Net-(R2C-Pad1)") (class "Default")
      (node (ref "R2C") (pin "1") (pinfunction "1_1") (pintype "passive"))
      (node (ref "TX") (pin "A") (pinfunction "A_A") (pintype "passive"))
    )
    (net (code "62") (name "Net-(R3A-Pad1)") (class "Default")
      (node (ref "R3A") (pin "1") (pinfunction "1_1") (pintype "passive"))
      (node (ref "USB_MICRO_B") (pin "D-") (pinfunction "D-_D-") (pintype "bidirectional"))
      (node (ref "Z1") (pin "1") (pinfunction "1_1") (pintype "passive"))
    )
    (net (code "63") (name "Net-(R3D-Pad1)") (class "Default")
      (node (ref "R3D") (pin "1") (pinfunction "1_1") (pintype "passive"))
      (node (ref "USB_MICRO_B") (pin "D+") (pinfunction "D+_D+") (pintype "bidirectional"))
      (node (ref "Z2") (pin "1") (pinfunction "1_1") (pintype "passive"))
    )
    (net (code "64") (name "Net-(U3-D+)") (class "Default")
      (node (ref "R3D") (pin "2") (pinfunction "2_2") (pintype "passive"))
      (node (ref "U3") (pin "29") (pinfunction "D+_29") (pintype "bidirectional"))
    )
    (net (code "65") (name "Net-(U3-D-)") (class "Default")
      (node (ref "R3A") (pin "2") (pinfunction "2_2") (pintype "passive"))
      (node (ref "U3") (pin "30") (pinfunction "D-_30") (pintype "bidirectional"))
    )
    (net (code "66") (name "Net-(U3-UCAP)") (class "Default")
      (node (ref "C8") (pin "1") (pinfunction "1_1") (pintype "passive"))
      (node (ref "U3") (pin "27") (pinfunction "UCAP_27") (pintype "passive"))
    )
    (net (code "67") (name "Net-(U3-UGND)") (class "Default")
      (node (ref "L1") (pin "1") (pinfunction "1_1") (pintype "passive"))
      (node (ref "SJ1") (pin "2") (pinfunction "2_2") (pintype "passive"))
      (node (ref "U3") (pin "28") (pinfunction "UGND_28") (pintype "power_in"))
      (node (ref "USB_MICRO_B") (pin "GND") (pinfunction "GND_GND") (pintype "power_in"))
    )
    (net (code "68") (name "Net-(U3-XTAL1)") (class "Default")
      (node (ref "C9") (pin "2") (pinfunction "2_2") (pintype "passive"))
      (node (ref "R1") (pin "2") (pinfunction "2_2") (pintype "passive"))
      (node (ref "U3") (pin "1") (pinfunction "XTAL1_1") (pintype "bidirectional"))
      (node (ref "Y1") (pin "2") (pinfunction "2_2") (pintype "passive"))
    )
    (net (code "69") (name "Net-(U3-XTAL2{slash}PC0)") (class "Default")
      (node (ref "C11") (pin "2") (pinfunction "2_2") (pintype "passive"))
      (node (ref "R1") (pin "1") (pinfunction "1_1") (pintype "passive"))
      (node (ref "U3") (pin "2") (pinfunction "XTAL2/PC0_2") (pintype "bidirectional"))
      (node (ref "Y1") (pin "1") (pinfunction "1_1") (pintype "passive"))
    )
    (net (code "70") (name "Net-(U4-PB6(XTAL1{slash}TOSC1))") (class "Default")
      (node (ref "R2") (pin "2") (pinfunction "2_2") (pintype "passive"))
      (node (ref "U4") (pin "7") (pinfunction "PB6(XTAL1/TOSC1)_7") (pintype "bidirectional"))
      (node (ref "Y2") (pin "1") (pinfunction "1_1") (pintype "passive"))
    )
    (net (code "71") (name "Net-(U4-PB7(XTAL2{slash}TOSC2))") (class "Default")
      (node (ref "R2") (pin "1") (pinfunction "1_1") (pintype "passive"))
      (node (ref "U4") (pin "8") (pinfunction "PB7(XTAL2/TOSC2)_8") (pintype "bidirectional"))
      (node (ref "Y2") (pin "3") (pinfunction "3_3") (pintype "passive"))
    )
    (net (code "72") (name "Net-(U5B--IN)") (class "Default")
      (node (ref "R2A") (pin "1") (pinfunction "1_1") (pintype "passive"))
      (node (ref "U5") (pin "6") (pinfunction "-IN_6") (pintype "input"))
      (node (ref "U5") (pin "7") (pinfunction "OUT_7") (pintype "output"))
    )
    (net (code "73") (name "unconnected-(CON1-PadNC)") (class "Default")
      (node (ref "CON1") (pin "NC") (pinfunction "NC_NC") (pintype "no_connect"))
    )
    (net (code "74") (name "unconnected-(U2-NC{slash}FB-Pad4)") (class "Default")
      (node (ref "U2") (pin "4") (pinfunction "NC/FB_4") (pintype "passive"))
    )
    (net (code "75") (name "unconnected-(USB_MICRO_B-PadID)") (class "Default")
      (node (ref "USB_MICRO_B") (pin "ID") (pinfunction "ID_ID") (pintype "bidirectional"))
    )
  )
)
